# Buffered_mult.net
KiCad netlist of a schematic drawn in EAGLE
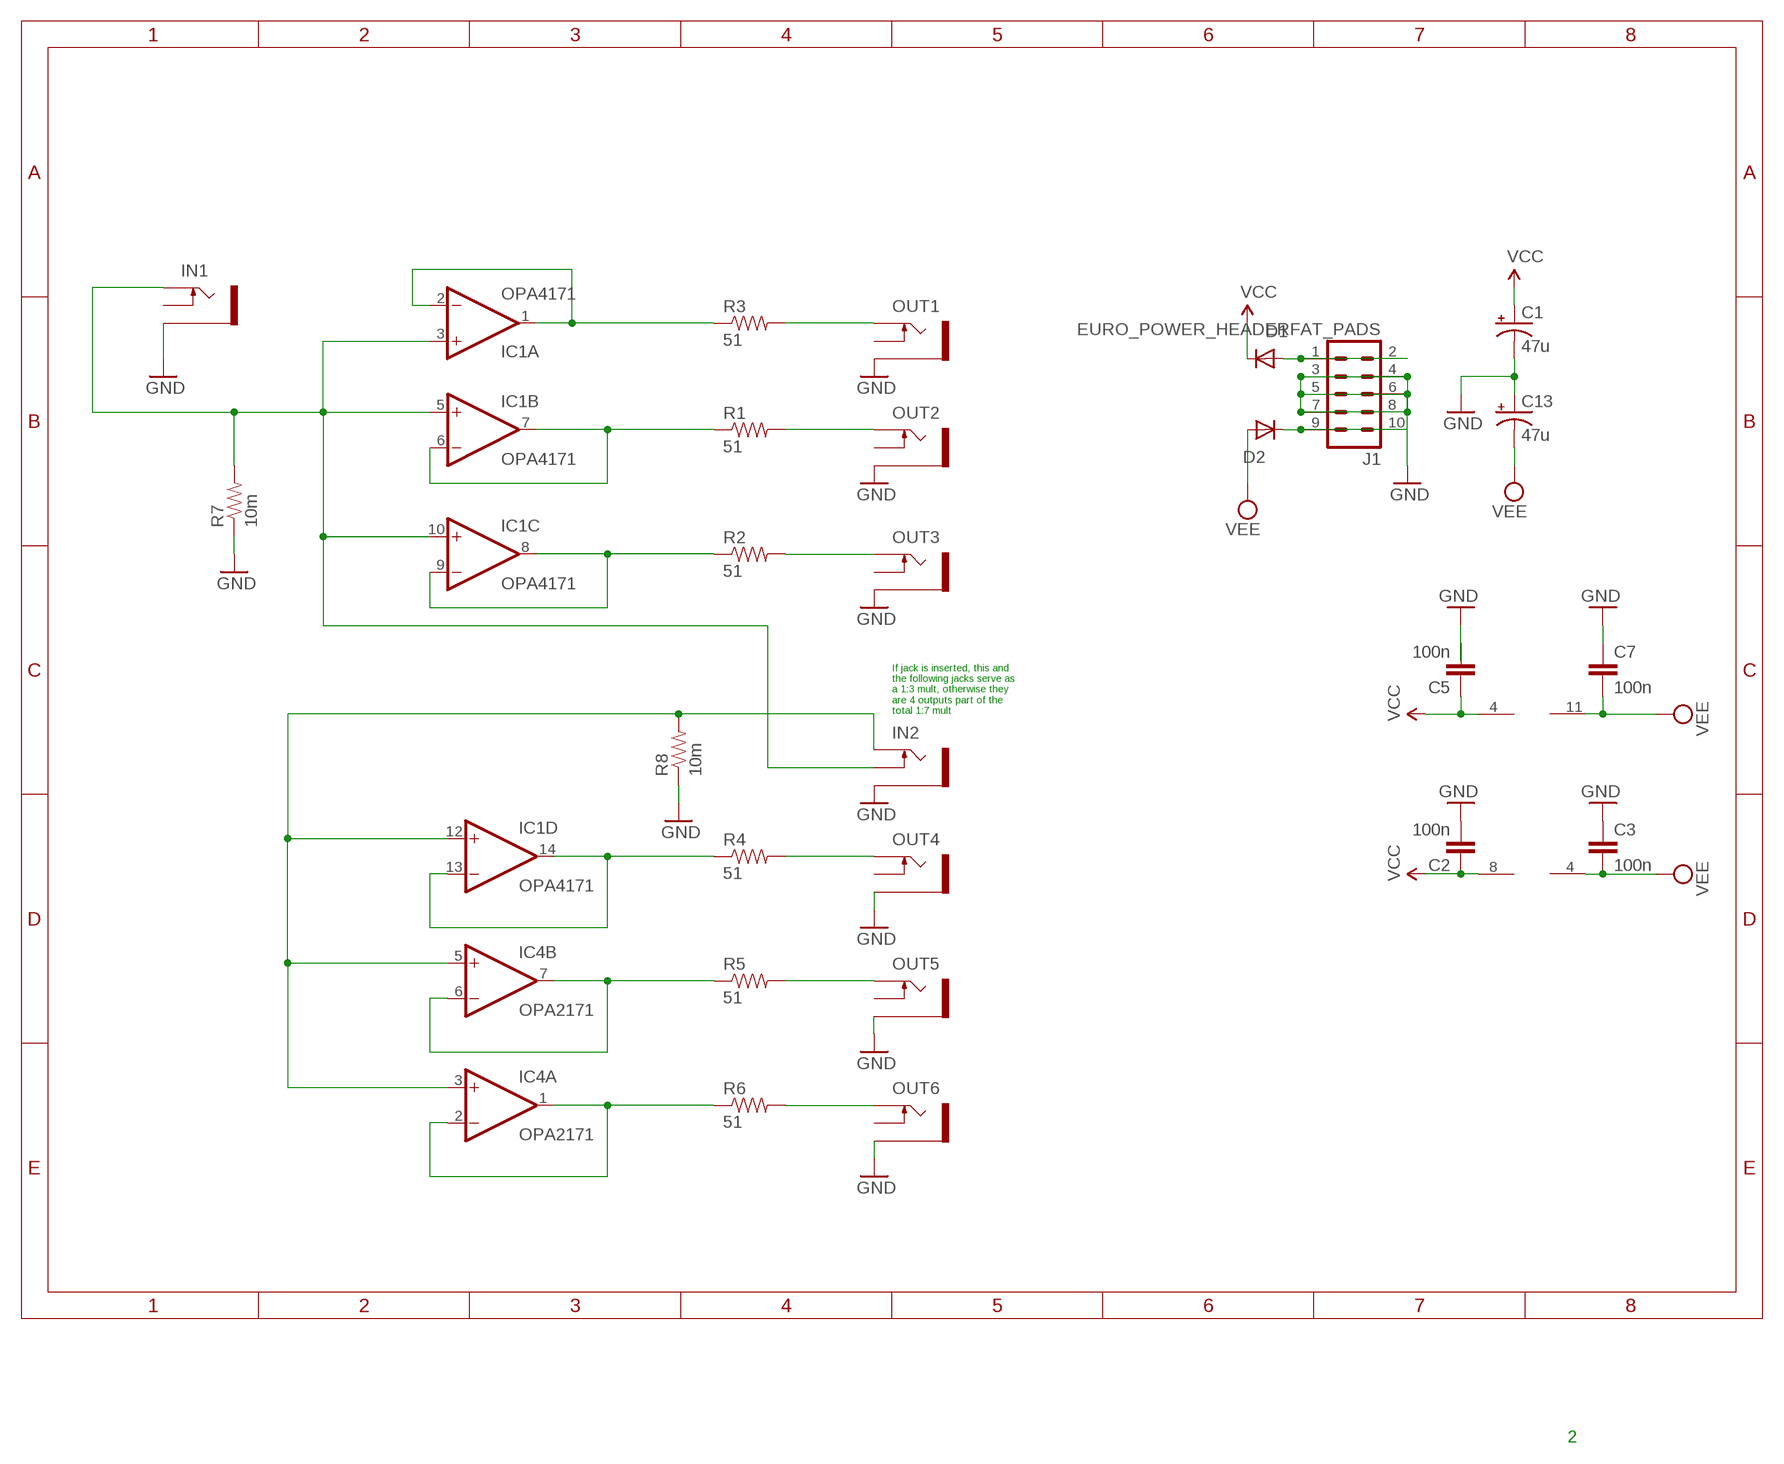
[diagram p0: schematic, sheet 1]

(export (version "E")
  (design (tool "Eeschema 10.0.6"))
  (components
    (comp (ref "C1")
      (value "47u")
      (footprint "eagle-import:PANASONIC_D")
      (libsource (lib "eagle-import") (part "CPOL-USD"))
    )
    (comp (ref "C2")
      (value "100n")
      (footprint "eagle-import:1206")
      (libsource (lib "eagle-import") (part "CAP1206"))
    )
    (comp (ref "C3")
      (value "100n")
      (footprint "eagle-import:1206")
      (libsource (lib "eagle-import") (part "CAP1206"))
    )
    (comp (ref "C5")
      (value "100n")
      (footprint "eagle-import:1206")
      (libsource (lib "eagle-import") (part "CAP1206"))
    )
    (comp (ref "C7")
      (value "100n")
      (footprint "eagle-import:1206")
      (libsource (lib "eagle-import") (part "CAP1206"))
    )
    (comp (ref "C13")
      (value "47u")
      (footprint "eagle-import:PANASONIC_D")
      (libsource (lib "eagle-import") (part "CPOL-USD"))
    )
    (comp (ref "D1")
      (value "1N5819HW")
      (footprint "eagle-import:SOD123")
      (libsource (lib "eagle-import") (part "DIODE-SOD123"))
    )
    (comp (ref "D2")
      (value "1N5819HW")
      (footprint "eagle-import:SOD123")
      (libsource (lib "eagle-import") (part "DIODE-SOD123"))
    )
    (comp (ref "IC1")
      (value "OPA4171")
      (footprint "eagle-import:TSSOP14")
      (libsource (lib "eagle-import") (part "TL074PW"))
    )
    (comp (ref "IC4")
      (value "OPA2171")
      (footprint "eagle-import:SO08")
      (libsource (lib "eagle-import") (part "TL072D"))
    )
    (comp (ref "IN1")
      (value "PJ302M")
      (footprint "eagle-import:PJ302M")
      (libsource (lib "eagle-import") (part "PJ302M"))
    )
    (comp (ref "IN2")
      (value "PJ302M")
      (footprint "eagle-import:PJ302M")
      (libsource (lib "eagle-import") (part "PJ302M"))
    )
    (comp (ref "J1")
      (value "EURO_POWER_HEADERFAT_PADS")
      (footprint "eagle-import:EURO_PWR_HEADER_FAT")
      (libsource (lib "eagle-import") (part "EURO_POWER_HEADERFAT_PADS"))
    )
    (comp (ref "OUT1")
      (value "PJ302M")
      (footprint "eagle-import:PJ302M")
      (libsource (lib "eagle-import") (part "PJ302M"))
    )
    (comp (ref "OUT2")
      (value "PJ302M")
      (footprint "eagle-import:PJ302M")
      (libsource (lib "eagle-import") (part "PJ302M"))
    )
    (comp (ref "OUT3")
      (value "PJ302M")
      (footprint "eagle-import:PJ302M")
      (libsource (lib "eagle-import") (part "PJ302M"))
    )
    (comp (ref "OUT4")
      (value "PJ302M")
      (footprint "eagle-import:PJ302M")
      (libsource (lib "eagle-import") (part "PJ302M"))
    )
    (comp (ref "OUT5")
      (value "PJ302M")
      (footprint "eagle-import:PJ302M")
      (libsource (lib "eagle-import") (part "PJ302M"))
    )
    (comp (ref "OUT6")
      (value "PJ302M")
      (footprint "eagle-import:PJ302M")
      (libsource (lib "eagle-import") (part "PJ302M"))
    )
    (comp (ref "R1")
      (value "51")
      (footprint "eagle-import:1206")
      (libsource (lib "eagle-import") (part "RESISTOR1206"))
    )
    (comp (ref "R2")
      (value "51")
      (footprint "eagle-import:1206")
      (libsource (lib "eagle-import") (part "RESISTOR1206"))
    )
    (comp (ref "R3")
      (value "51")
      (footprint "eagle-import:1206")
      (libsource (lib "eagle-import") (part "RESISTOR1206"))
    )
    (comp (ref "R4")
      (value "51")
      (footprint "eagle-import:1206")
      (libsource (lib "eagle-import") (part "RESISTOR1206"))
    )
    (comp (ref "R5")
      (value "51")
      (footprint "eagle-import:1206")
      (libsource (lib "eagle-import") (part "RESISTOR1206"))
    )
    (comp (ref "R6")
      (value "51")
      (footprint "eagle-import:1206")
      (libsource (lib "eagle-import") (part "RESISTOR1206"))
    )
    (comp (ref "R7")
      (value "10m")
      (footprint "eagle-import:1206")
      (libsource (lib "eagle-import") (part "RESISTOR1206"))
    )
    (comp (ref "R8")
      (value "10m")
      (footprint "eagle-import:1206")
      (libsource (lib "eagle-import") (part "RESISTOR1206"))
    )
  )
  (nets
    (net (code "1") (name "GND") (class "Default")
      (node (ref "C1") (pin "-") (pinfunction "-_-") (pintype "passive"))
      (node (ref "C13") (pin "+") (pinfunction "+_+") (pintype "passive"))
      (node (ref "C2") (pin "2") (pinfunction "2_2") (pintype "passive"))
      (node (ref "C3") (pin "1") (pinfunction "1_1") (pintype "passive"))
      (node (ref "C5") (pin "2") (pinfunction "2_2") (pintype "passive"))
      (node (ref "C7") (pin "1") (pinfunction "1_1") (pintype "passive"))
      (node (ref "IN1") (pin "GND") (pinfunction "SLEEVE_GND") (pintype "passive"))
      (node (ref "IN2") (pin "GND") (pinfunction "SLEEVE_GND") (pintype "passive"))
      (node (ref "J1") (pin "3") (pinfunction "3_3") (pintype "passive"))
      (node (ref "J1") (pin "4") (pinfunction "4_4") (pintype "passive"))
      (node (ref "J1") (pin "5") (pinfunction "5_5") (pintype "passive"))
      (node (ref "J1") (pin "6") (pinfunction "6_6") (pintype "passive"))
      (node (ref "J1") (pin "7") (pinfunction "7_7") (pintype "passive"))
      (node (ref "J1") (pin "8") (pinfunction "8_8") (pintype "passive"))
      (node (ref "OUT1") (pin "GND") (pinfunction "SLEEVE_GND") (pintype "passive"))
      (node (ref "OUT2") (pin "GND") (pinfunction "SLEEVE_GND") (pintype "passive"))
      (node (ref "OUT3") (pin "GND") (pinfunction "SLEEVE_GND") (pintype "passive"))
      (node (ref "OUT4") (pin "GND") (pinfunction "SLEEVE_GND") (pintype "passive"))
      (node (ref "OUT5") (pin "GND") (pinfunction "SLEEVE_GND") (pintype "passive"))
      (node (ref "OUT6") (pin "GND") (pinfunction "SLEEVE_GND") (pintype "passive"))
      (node (ref "R7") (pin "1") (pinfunction "1_1") (pintype "passive"))
      (node (ref "R8") (pin "1") (pinfunction "1_1") (pintype "passive"))
    )
    (net (code "2") (name "Net-(D1-PadA)") (class "Default")
      (node (ref "D1") (pin "A") (pinfunction "A_A") (pintype "passive"))
      (node (ref "J1") (pin "1") (pinfunction "1_1") (pintype "passive"))
      (node (ref "J1") (pin "2") (pinfunction "2_2") (pintype "passive"))
    )
    (net (code "3") (name "Net-(D2-PadC)") (class "Default")
      (node (ref "D2") (pin "C") (pinfunction "C_C") (pintype "passive"))
      (node (ref "J1") (pin "10") (pinfunction "10_10") (pintype "passive"))
      (node (ref "J1") (pin "9") (pinfunction "9_9") (pintype "passive"))
    )
    (net (code "4") (name "Net-(IC1A-+IN)") (class "Default")
      (node (ref "IC1") (pin "10") (pinfunction "+IN_10") (pintype "input"))
      (node (ref "IC1") (pin "3") (pinfunction "+IN_3") (pintype "input"))
      (node (ref "IC1") (pin "5") (pinfunction "+IN_5") (pintype "input"))
      (node (ref "IN1") (pin "TIP") (pinfunction "TIP_TIP") (pintype "passive"))
      (node (ref "IN2") (pin "SW") (pinfunction "SWITCH_SW") (pintype "passive"))
      (node (ref "R7") (pin "2") (pinfunction "2_2") (pintype "passive"))
    )
    (net (code "5") (name "Net-(IC1A--IN)") (class "Default")
      (node (ref "IC1") (pin "1") (pinfunction "OUT_1") (pintype "output"))
      (node (ref "IC1") (pin "2") (pinfunction "-IN_2") (pintype "input"))
      (node (ref "R3") (pin "1") (pinfunction "1_1") (pintype "passive"))
    )
    (net (code "6") (name "Net-(IC1B--IN)") (class "Default")
      (node (ref "IC1") (pin "6") (pinfunction "-IN_6") (pintype "input"))
      (node (ref "IC1") (pin "7") (pinfunction "OUT_7") (pintype "output"))
      (node (ref "R1") (pin "1") (pinfunction "1_1") (pintype "passive"))
    )
    (net (code "7") (name "Net-(IC1C--IN)") (class "Default")
      (node (ref "IC1") (pin "8") (pinfunction "OUT_8") (pintype "output"))
      (node (ref "IC1") (pin "9") (pinfunction "-IN_9") (pintype "input"))
      (node (ref "R2") (pin "1") (pinfunction "1_1") (pintype "passive"))
    )
    (net (code "8") (name "Net-(IC1D-+IN)") (class "Default")
      (node (ref "IC1") (pin "12") (pinfunction "+IN_12") (pintype "input"))
      (node (ref "IC4") (pin "3") (pinfunction "+IN_3") (pintype "input"))
      (node (ref "IC4") (pin "5") (pinfunction "+IN_5") (pintype "input"))
      (node (ref "IN2") (pin "TIP") (pinfunction "TIP_TIP") (pintype "passive"))
      (node (ref "R8") (pin "2") (pinfunction "2_2") (pintype "passive"))
    )
    (net (code "9") (name "Net-(IC1D--IN)") (class "Default")
      (node (ref "IC1") (pin "13") (pinfunction "-IN_13") (pintype "input"))
      (node (ref "IC1") (pin "14") (pinfunction "OUT_14") (pintype "output"))
      (node (ref "R4") (pin "1") (pinfunction "1_1") (pintype "passive"))
    )
    (net (code "10") (name "Net-(IC4A--IN)") (class "Default")
      (node (ref "IC4") (pin "1") (pinfunction "OUT_1") (pintype "output"))
      (node (ref "IC4") (pin "2") (pinfunction "-IN_2") (pintype "input"))
      (node (ref "R6") (pin "1") (pinfunction "1_1") (pintype "passive"))
    )
    (net (code "11") (name "Net-(IC4B--IN)") (class "Default")
      (node (ref "IC4") (pin "6") (pinfunction "-IN_6") (pintype "input"))
      (node (ref "IC4") (pin "7") (pinfunction "OUT_7") (pintype "output"))
      (node (ref "R5") (pin "1") (pinfunction "1_1") (pintype "passive"))
    )
    (net (code "12") (name "Net-(OUT1-PadTIP)") (class "Default")
      (node (ref "OUT1") (pin "TIP") (pinfunction "TIP_TIP") (pintype "passive"))
      (node (ref "R3") (pin "2") (pinfunction "2_2") (pintype "passive"))
    )
    (net (code "13") (name "Net-(OUT2-PadTIP)") (class "Default")
      (node (ref "OUT2") (pin "TIP") (pinfunction "TIP_TIP") (pintype "passive"))
      (node (ref "R1") (pin "2") (pinfunction "2_2") (pintype "passive"))
    )
    (net (code "14") (name "Net-(OUT3-PadTIP)") (class "Default")
      (node (ref "OUT3") (pin "TIP") (pinfunction "TIP_TIP") (pintype "passive"))
      (node (ref "R2") (pin "2") (pinfunction "2_2") (pintype "passive"))
    )
    (net (code "15") (name "Net-(OUT4-PadTIP)") (class "Default")
      (node (ref "OUT4") (pin "TIP") (pinfunction "TIP_TIP") (pintype "passive"))
      (node (ref "R4") (pin "2") (pinfunction "2_2") (pintype "passive"))
    )
    (net (code "16") (name "Net-(OUT5-PadTIP)") (class "Default")
      (node (ref "OUT5") (pin "TIP") (pinfunction "TIP_TIP") (pintype "passive"))
      (node (ref "R5") (pin "2") (pinfunction "2_2") (pintype "passive"))
    )
    (net (code "17") (name "Net-(OUT6-PadTIP)") (class "Default")
      (node (ref "OUT6") (pin "TIP") (pinfunction "TIP_TIP") (pintype "passive"))
      (node (ref "R6") (pin "2") (pinfunction "2_2") (pintype "passive"))
    )
    (net (code "18") (name "VCC") (class "Default")
      (node (ref "C1") (pin "+") (pinfunction "+_+") (pintype "passive"))
      (node (ref "C2") (pin "1") (pinfunction "1_1") (pintype "passive"))
      (node (ref "C5") (pin "1") (pinfunction "1_1") (pintype "passive"))
      (node (ref "D1") (pin "C") (pinfunction "C_C") (pintype "passive"))
      (node (ref "IC1") (pin "4") (pinfunction "V+_4") (pintype "power_in"))
      (node (ref "IC4") (pin "8") (pinfunction "V+_8") (pintype "power_in"))
    )
    (net (code "19") (name "VEE") (class "Default")
      (node (ref "C13") (pin "-") (pinfunction "-_-") (pintype "passive"))
      (node (ref "C3") (pin "2") (pinfunction "2_2") (pintype "passive"))
      (node (ref "C7") (pin "2") (pinfunction "2_2") (pintype "passive"))
      (node (ref "D2") (pin "A") (pinfunction "A_A") (pintype "passive"))
      (node (ref "IC1") (pin "11") (pinfunction "V-_11") (pintype "power_in"))
      (node (ref "IC4") (pin "4") (pinfunction "V-_4") (pintype "power_in"))
    )
    (net (code "20") (name "unconnected-(IN1-SWITCH-PadSW)") (class "Default")
      (node (ref "IN1") (pin "SW") (pinfunction "SWITCH_SW") (pintype "passive"))
    )
    (net (code "21") (name "unconnected-(OUT1-SWITCH-PadSW)") (class "Default")
      (node (ref "OUT1") (pin "SW") (pinfunction "SWITCH_SW") (pintype "passive"))
    )
    (net (code "22") (name "unconnected-(OUT2-SWITCH-PadSW)") (class "Default")
      (node (ref "OUT2") (pin "SW") (pinfunction "SWITCH_SW") (pintype "passive"))
    )
    (net (code "23") (name "unconnected-(OUT3-SWITCH-PadSW)") (class "Default")
      (node (ref "OUT3") (pin "SW") (pinfunction "SWITCH_SW") (pintype "passive"))
    )
    (net (code "24") (name "unconnected-(OUT4-SWITCH-PadSW)") (class "Default")
      (node (ref "OUT4") (pin "SW") (pinfunction "SWITCH_SW") (pintype "passive"))
    )
    (net (code "25") (name "unconnected-(OUT5-SWITCH-PadSW)") (class "Default")
      (node (ref "OUT5") (pin "SW") (pinfunction "SWITCH_SW") (pintype "passive"))
    )
    (net (code "26") (name "unconnected-(OUT6-SWITCH-PadSW)") (class "Default")
      (node (ref "OUT6") (pin "SW") (pinfunction "SWITCH_SW") (pintype "passive"))
    )
  )
)
